# Ind_current_sensor_U.net
KiCad netlist of a schematic drawn in Altium Designer
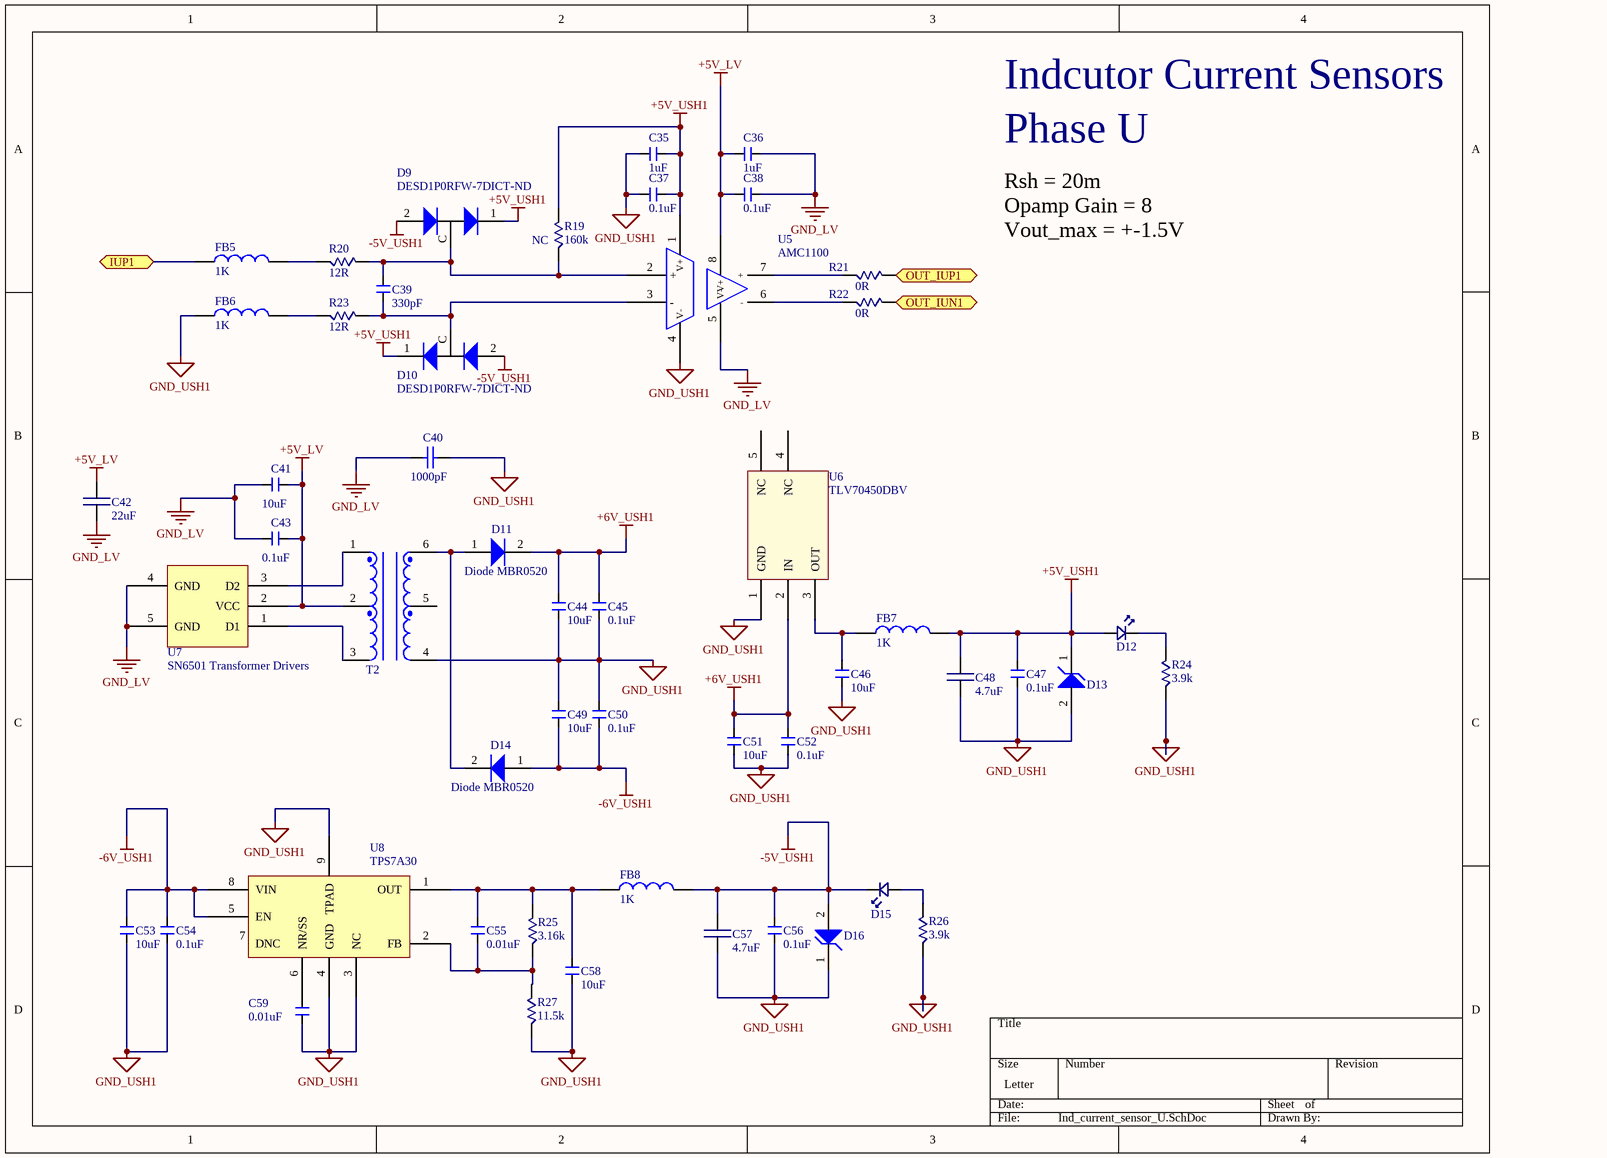
[diagram p0: Ind_current_sensor_U.SchDoc]

(export (version "E")
  (design (tool "Eeschema 10.0.6"))
  (components
    (comp (ref "C35")
      (value "1uF")
      (footprint "0603 (1608 Metric)")
      (description "CAP CER 1UF 50V X5R 0603")
      (fields (field (name "PART") "1276-1860-1-ND") (field (name "Comment") "Cap 0603_new"))
      (libsource (lib "Library_Microgrid") (part "Cap 0603_new"))
    )
    (comp (ref "C36")
      (value "1uF")
      (footprint "0603 (1608 Metric)")
      (description "CAP CER 1UF 50V X5R 0603")
      (fields (field (name "PART") "1276-1860-1-ND") (field (name "Comment") "Cap 0603_new"))
      (libsource (lib "Library_Microgrid") (part "Cap 0603_new"))
    )
    (comp (ref "C37")
      (value "0.1uF")
      (footprint "0603 (1608 Metric)")
      (description "CAP CER 0.1UF 50V Y5V 0603")
      (fields (field (name "PART") "311-1343-6-ND") (field (name "Comment") "Cap 0603_new"))
      (libsource (lib "Library_Microgrid") (part "Cap 0603_new"))
    )
    (comp (ref "C38")
      (value "0.1uF")
      (footprint "0603 (1608 Metric)")
      (description "CAP CER 0.1UF 50V Y5V 0603")
      (fields (field (name "PART") "311-1343-6-ND") (field (name "Comment") "Cap 0603_new"))
      (libsource (lib "Library_Microgrid") (part "Cap 0603_new"))
    )
    (comp (ref "C39")
      (value "330pF")
      (footprint "0603 (1608 Metric)")
      (description "CAP CER 330PF 50V C0G 0603")
      (fields (field (name "PART") "445-7033-2-ND") (field (name "Comment") "Cap 0603_new"))
      (libsource (lib "Library_Microgrid") (part "Cap 0603_new"))
    )
    (comp (ref "C40")
      (value "1000pF")
      (footprint "RAD-0.3")
      (description "CAP CER 1000PF 1KV Y5P RADIAL")
      (fields
        (field (name "PART") "1251PH-ND")
        (field (name "Comment") "Cap TH")
        (field (name "PUBLISHER") "Altium Limited")
      )
      (libsource (lib "Miscellaneous Devices") (part "Cap"))
    )
    (comp (ref "C41")
      (value "10uF")
      (footprint "0603 (1608 Metric)")
      (description "CAP CER 10UF 35V X5R 0805")
      (fields (field (name "PART") "490-10515-1-ND") (field (name "Comment") "Cap 0603_new"))
      (libsource (lib "Library_Microgrid") (part "Cap 0603_new"))
    )
    (comp (ref "C42")
      (value "22uF")
      (footprint "0805 (2012 metric)")
      (description "CAP CER 22UF 35V X5R 0805")
      (fields (field (name "PART") "445-14428-1-ND") (field (name "Comment") "Cap 0805"))
      (libsource (lib "Library_Microgrid") (part "Cap 0805"))
    )
    (comp (ref "C43")
      (value "0.1uF")
      (footprint "0603 (1608 Metric)")
      (description "CAP CER 0.1UF 50V Y5V 0603")
      (fields (field (name "PART") "311-1343-6-ND") (field (name "Comment") "Cap 0603_new"))
      (libsource (lib "Library_Microgrid") (part "Cap 0603_new"))
    )
    (comp (ref "C44")
      (value "10uF")
      (footprint "0603 (1608 Metric)")
      (description "CAP CER 10UF 35V X5R 0805")
      (fields (field (name "PART") "490-10515-1-ND") (field (name "Comment") "Cap 0603_new"))
      (libsource (lib "Library_Microgrid") (part "Cap 0603_new"))
    )
    (comp (ref "C45")
      (value "0.1uF")
      (footprint "0603 (1608 Metric)")
      (description "CAP CER 0.1UF 50V Y5V 0603")
      (fields (field (name "PART") "311-1343-6-ND") (field (name "Comment") "Cap 0603_new"))
      (libsource (lib "Library_Microgrid") (part "Cap 0603_new"))
    )
    (comp (ref "C46")
      (value "10uF")
      (footprint "0603 (1608 Metric)")
      (description "CAP CER 10UF 35V X5R 0805")
      (fields (field (name "PART") "490-10515-1-ND") (field (name "Comment") "Cap 0603_new"))
      (libsource (lib "Library_Microgrid") (part "Cap 0603_new"))
    )
    (comp (ref "C47")
      (value "0.1uF")
      (footprint "0603 (1608 Metric)")
      (description "CAP CER 0.1UF 50V Y5V 0603")
      (fields (field (name "PART") "311-1343-6-ND") (field (name "Comment") "Cap 0603_new"))
      (libsource (lib "Library_Microgrid") (part "Cap 0603_new"))
    )
    (comp (ref "C48")
      (value "4.7uF")
      (footprint "0805 (2012 metric)")
      (description "CAP CER 4.7UF 50V X5R 0805")
      (fields (field (name "PART") "445-5980-1-ND") (field (name "Comment") "Cap 0805"))
      (libsource (lib "Library_Microgrid") (part "Cap 0805"))
    )
    (comp (ref "C49")
      (value "10uF")
      (footprint "0603 (1608 Metric)")
      (description "CAP CER 10UF 35V X5R 0805")
      (fields (field (name "PART") "490-10515-1-ND") (field (name "Comment") "Cap 0603_new"))
      (libsource (lib "Library_Microgrid") (part "Cap 0603_new"))
    )
    (comp (ref "C50")
      (value "0.1uF")
      (footprint "0603 (1608 Metric)")
      (description "CAP CER 0.1UF 50V Y5V 0603")
      (fields (field (name "PART") "311-1343-6-ND") (field (name "Comment") "Cap 0603_new"))
      (libsource (lib "Library_Microgrid") (part "Cap 0603_new"))
    )
    (comp (ref "C51")
      (value "10uF")
      (footprint "0603 (1608 Metric)")
      (description "CAP CER 10UF 35V X5R 0805")
      (fields (field (name "PART") "490-10515-1-ND") (field (name "Comment") "Cap 0603_new"))
      (libsource (lib "Library_Microgrid") (part "Cap 0603_new"))
    )
    (comp (ref "C52")
      (value "0.1uF")
      (footprint "0603 (1608 Metric)")
      (description "CAP CER 0.1UF 50V Y5V 0603")
      (fields (field (name "PART") "311-1343-6-ND") (field (name "Comment") "Cap 0603_new"))
      (libsource (lib "Library_Microgrid") (part "Cap 0603_new"))
    )
    (comp (ref "C53")
      (value "10uF")
      (footprint "0603 (1608 Metric)")
      (description "CAP CER 10UF 35V X5R 0805")
      (fields (field (name "PART") "490-10515-1-ND") (field (name "Comment") "Cap 0603_new"))
      (libsource (lib "Library_Microgrid") (part "Cap 0603_new"))
    )
    (comp (ref "C54")
      (value "0.1uF")
      (footprint "0603 (1608 Metric)")
      (description "CAP CER 0.1UF 50V Y5V 0603")
      (fields (field (name "PART") "311-1343-6-ND") (field (name "Comment") "Cap 0603_new"))
      (libsource (lib "Library_Microgrid") (part "Cap 0603_new"))
    )
    (comp (ref "C55")
      (value "0.01uF")
      (footprint "0603 (1608 Metric)")
      (description "CAP CER 10000PF 100V X7R 0603")
      (fields (field (name "PART") "478-7418-1-ND") (field (name "Comment") "Cap 0603_new"))
      (libsource (lib "Library_Microgrid") (part "Cap 0603_new"))
    )
    (comp (ref "C56")
      (value "0.1uF")
      (footprint "0603 (1608 Metric)")
      (description "CAP CER 0.1UF 50V Y5V 0603")
      (fields (field (name "PART") "311-1343-6-ND") (field (name "Comment") "Cap 0603_new"))
      (libsource (lib "Library_Microgrid") (part "Cap 0603_new"))
    )
    (comp (ref "C57")
      (value "4.7uF")
      (footprint "0805 (2012 metric)")
      (description "CAP CER 4.7UF 50V X5R 0805")
      (fields (field (name "PART") "445-5980-1-ND") (field (name "Comment") "Cap 0805"))
      (libsource (lib "Library_Microgrid") (part "Cap 0805"))
    )
    (comp (ref "C58")
      (value "10uF")
      (footprint "0603 (1608 Metric)")
      (description "CAP CER 10UF 35V X5R 0805")
      (fields (field (name "PART") "490-10515-1-ND") (field (name "Comment") "Cap 0603_new"))
      (libsource (lib "Library_Microgrid") (part "Cap 0603_new"))
    )
    (comp (ref "C59")
      (value "0.01uF")
      (footprint "0603 (1608 Metric)")
      (description "CAP CER 10000PF 100V X7R 0603")
      (fields (field (name "PART") "478-7418-1-ND") (field (name "Comment") "Cap 0603_new"))
      (libsource (lib "Library_Microgrid") (part "Cap 0603_new"))
    )
    (comp (ref "D9")
      (value "TVS - Diodes")
      (footprint "SOT323_ESD")
      (description "TVS DIODE 70VWM 8VC SOT323")
      (fields (field (name "PART") "DESD1P0RFW-7DICT-ND"))
      (libsource (lib "Library_Microgrid") (part "Diode_ESD"))
    )
    (comp (ref "D10")
      (value "TVS - Diodes")
      (footprint "SOT323_ESD")
      (description "TVS DIODE 70VWM 8VC SOT323")
      (fields (field (name "PART") "DESD1P0RFW-7DICT-ND"))
      (libsource (lib "Library_Microgrid") (part "Diode_ESD"))
    )
    (comp (ref "D11")
      (value "Diode MBR0520")
      (footprint "SOD-123")
      (description "DIODE SCHOTTKY 20V 500MA SOD123")
      (fields (field (name "PART") "MBR0520LT1GOSCT-ND"))
      (libsource (lib "Library_Microgrid") (part "Diode MBR0520"))
    )
    (comp (ref "D12")
      (value "LED")
      (footprint "0805 (2012 Metric) Diode")
      (description "LED 0805")
      (libsource (lib "Library_Microgrid") (part "LED"))
    )
    (comp (ref "D13")
      (value "*")
      (footprint "POWERDI")
      (description "DIODE ZENER POWERDI123")
      (fields (field (name "PART") "MMSZ5228B-FDICT-ND"))
      (libsource (lib "Library_Microgrid") (part "Diode Zener POWERDI123"))
    )
    (comp (ref "D14")
      (value "Diode MBR0520")
      (footprint "SOD-123")
      (description "DIODE SCHOTTKY 20V 500MA SOD123")
      (fields (field (name "PART") "MBR0520LT1GOSCT-ND"))
      (libsource (lib "Library_Microgrid") (part "Diode MBR0520"))
    )
    (comp (ref "D15")
      (value "LED")
      (footprint "0805 (2012 Metric) Diode")
      (description "LED 0805")
      (libsource (lib "Library_Microgrid") (part "LED"))
    )
    (comp (ref "D16")
      (value "*")
      (footprint "POWERDI")
      (description "DIODE ZENER POWERDI123")
      (fields (field (name "PART") "MMSZ5228B-FDICT-ND"))
      (libsource (lib "Library_Microgrid") (part "Diode Zener POWERDI123"))
    )
    (comp (ref "FB5")
      (value "1K")
      (footprint "0603 (1608 Metric)")
      (description "FERRITE BEAD 1 KOHM 0603 1LN")
      (fields (field (name "PART") "445-8672-1-ND") (field (name "Comment") "Ferrite bead"))
      (libsource (lib "Library_Microgrid") (part "Ferrite bead"))
    )
    (comp (ref "FB6")
      (value "1K")
      (footprint "0603 (1608 Metric)")
      (description "FERRITE BEAD 1 KOHM 0603 1LN")
      (fields (field (name "PART") "445-8672-1-ND") (field (name "Comment") "Ferrite bead"))
      (libsource (lib "Library_Microgrid") (part "Ferrite bead"))
    )
    (comp (ref "FB7")
      (value "1K")
      (footprint "0603 (1608 Metric)")
      (description "FERRITE BEAD 1 KOHM 0603 1LN")
      (fields (field (name "PART") "445-8672-1-ND") (field (name "Comment") "Ferrite bead"))
      (libsource (lib "Library_Microgrid") (part "Ferrite bead"))
    )
    (comp (ref "FB8")
      (value "1K")
      (footprint "0603 (1608 Metric)")
      (description "FERRITE BEAD 1 KOHM 0603 1LN")
      (fields (field (name "PART") "445-8672-1-ND") (field (name "Comment") "Ferrite bead"))
      (libsource (lib "Library_Microgrid") (part "Ferrite bead"))
    )
    (comp (ref "R19")
      (value "NC")
      (footprint "0603 (1608 Metric)")
      (description "Resistor 0603")
      (fields (field (name "ALTIUM_VALUE") "160k"))
      (libsource (lib "Library_Microgrid") (part "Resistor 0603"))
    )
    (comp (ref "R20")
      (value "12R")
      (footprint "1206")
      (description "12 Ohm ±0.5% 0.25W, 1/4W Chip Resistor 1206")
      (fields (field (name "PART") "311-2961-1-ND") (field (name "Comment") "Resistor 1206"))
      (libsource (lib "Library_Microgrid") (part "Resistor 1206"))
    )
    (comp (ref "R21")
      (value "0R")
      (footprint "0603 (1608 Metric)")
      (description "RES SMD 10 OHM 0.05% 1/10W 0603")
      (fields (field (name "PART") "RNCF0603AKT10R0CT-ND") (field (name "Comment") "Resistor 0603"))
      (libsource (lib "Library_Microgrid") (part "Resistor 0603"))
    )
    (comp (ref "R22")
      (value "0R")
      (footprint "0603 (1608 Metric)")
      (description "RES SMD 10 OHM 0.05% 1/10W 0603")
      (fields (field (name "PART") "RNCF0603AKT10R0CT-ND") (field (name "Comment") "Resistor 0603"))
      (libsource (lib "Library_Microgrid") (part "Resistor 0603"))
    )
    (comp (ref "R23")
      (value "12R")
      (footprint "1206")
      (description "12 Ohm ±0.5% 0.25W, 1/4W Chip Resistor 1206")
      (fields (field (name "PART") "311-2961-1-ND") (field (name "Comment") "Resistor 1206"))
      (libsource (lib "Library_Microgrid") (part "Resistor 1206"))
    )
    (comp (ref "R24")
      (value "3.9k")
      (footprint "0603 (1608 Metric)")
      (description "RES SMD 3.9K OHM 5% 1/10W 0603")
      (fields (field (name "PART") "541-3.9KGCT-ND") (field (name "Comment") "Resistor 0603"))
      (libsource (lib "Library_Microgrid") (part "Resistor 0603"))
    )
    (comp (ref "R25")
      (value "3.16k")
      (footprint "0603 (1608 Metric)")
      (description "RES SMD 3.16K OHM 1% 1/10W 0603")
      (fields (field (name "PART") "311-3.16KHRCT-ND") (field (name "Comment") "Resistor 0603"))
      (libsource (lib "Library_Microgrid") (part "Resistor 0603"))
    )
    (comp (ref "R26")
      (value "3.9k")
      (footprint "0603 (1608 Metric)")
      (description "RES SMD 3.9K OHM 5% 1/10W 0603")
      (fields (field (name "PART") "541-3.9KGCT-ND") (field (name "Comment") "Resistor 0603"))
      (libsource (lib "Library_Microgrid") (part "Resistor 0603"))
    )
    (comp (ref "R27")
      (value "11.5k")
      (footprint "0603 (1608 Metric)")
      (description "RES SMD 11.5K OHM 1% 1/10W 0603")
      (fields (field (name "PART") "541-11.5KHCT-ND") (field (name "Comment") "Resistor 0603"))
      (libsource (lib "Library_Microgrid") (part "Resistor 0603"))
    )
    (comp (ref "T2")
      (value "750313769")
      (footprint "Xmr SN6501")
      (description "TRANSFORMER SMD TR1.7 SN6501")
      (fields (field (name "PART") "1297-1107-1-ND"))
      (libsource (lib "Library_Microgrid") (part "750313769"))
    )
    (comp (ref "U5")
      (value "AMC1100")
      (footprint "SOIC8")
      (description "IC OPAMP ISOLATION 100KHZ 8SOIC")
      (fields (field (name "PART") "296-38822-5-ND"))
      (libsource (lib "Library_Microgrid") (part "AMC1100"))
    )
    (comp (ref "U6")
      (value "TLV70450DBV")
      (footprint "SOT23-5")
      (description "IC REG LDO 5V 0.15A SOT23-5")
      (fields (field (name "PART") "296-39287-1-ND"))
      (libsource (lib "Library_Microgrid") (part "TLV70450DBV"))
    )
    (comp (ref "U7")
      (value "SN6501 Transformer Drivers")
      (footprint "SOT23-5")
      (description "IC REG CONV PWR SUPPLIES SOT23-5")
      (fields (field (name "PART") "296-37700-1-ND"))
      (libsource (lib "Library_Microgrid") (part "SN6501"))
    )
    (comp (ref "U8")
      (value "TPS7A30")
      (footprint "8-TSSOP")
      (description "IC REG LDO NEG ADJ 0.2A 8MSOP")
      (fields (field (name "PART") "296-27750-1-ND"))
      (libsource (lib "Library_Microgrid") (part "TPS7A30"))
    )
  )
  (nets
    (net (code "1") (name "+5V_LV") (class "Default")
      (node (ref "C36") (pin "1") (pinfunction "OUT_1") (pintype "passive"))
      (node (ref "C38") (pin "1") (pinfunction "OUT_1") (pintype "passive"))
      (node (ref "C41") (pin "2") (pinfunction "OUT_2") (pintype "passive"))
      (node (ref "C42") (pin "2") (pinfunction "OUT_2") (pintype "passive"))
      (node (ref "C43") (pin "2") (pinfunction "OUT_2") (pintype "passive"))
      (node (ref "T2") (pin "2") (pinfunction "1_2") (pintype "passive"))
      (node (ref "U5") (pin "8") (pinfunction "V+_8") (pintype "passive"))
      (node (ref "U7") (pin "2") (pinfunction "VCC_2") (pintype "passive"))
    )
    (net (code "2") (name "+5V_USH1") (class "Default")
      (node (ref "C35") (pin "2") (pinfunction "OUT_2") (pintype "passive"))
      (node (ref "C37") (pin "2") (pinfunction "OUT_2") (pintype "passive"))
      (node (ref "C47") (pin "2") (pinfunction "OUT_2") (pintype "passive"))
      (node (ref "C48") (pin "2") (pinfunction "OUT_2") (pintype "passive"))
      (node (ref "D10") (pin "1") (pinfunction "Anode_1") (pintype "passive"))
      (node (ref "D12") (pin "A") (pinfunction "A_A") (pintype "passive"))
      (node (ref "D13") (pin "1") (pinfunction "Anode_1") (pintype "passive"))
      (node (ref "D9") (pin "1") (pinfunction "Anode_1") (pintype "passive"))
      (node (ref "FB7") (pin "2") (pinfunction "OUT_2") (pintype "passive"))
      (node (ref "R19") (pin "2") (pinfunction "A_2") (pintype "passive"))
      (node (ref "U5") (pin "1") (pinfunction "V+_1") (pintype "passive"))
    )
    (net (code "3") (name "+6V_USH1") (class "Default")
      (node (ref "C44") (pin "2") (pinfunction "OUT_2") (pintype "passive"))
      (node (ref "C45") (pin "2") (pinfunction "OUT_2") (pintype "passive"))
      (node (ref "C51") (pin "2") (pinfunction "OUT_2") (pintype "passive"))
      (node (ref "C52") (pin "2") (pinfunction "OUT_2") (pintype "passive"))
      (node (ref "D11") (pin "2") (pinfunction "Anode_2") (pintype "passive"))
      (node (ref "U6") (pin "2") (pinfunction "IN_2") (pintype "passive"))
    )
    (net (code "4") (name "-5V_USH1") (class "Default")
      (node (ref "C56") (pin "2") (pinfunction "OUT_2") (pintype "passive"))
      (node (ref "C57") (pin "2") (pinfunction "OUT_2") (pintype "passive"))
      (node (ref "D10") (pin "2") (pinfunction "Anode_2") (pintype "passive"))
      (node (ref "D15") (pin "K") (pinfunction "K_K") (pintype "passive"))
      (node (ref "D16") (pin "2") (pinfunction "Anode_2") (pintype "passive"))
      (node (ref "D9") (pin "2") (pinfunction "Anode_2") (pintype "passive"))
      (node (ref "FB8") (pin "2") (pinfunction "OUT_2") (pintype "passive"))
    )
    (net (code "5") (name "-6V_USH1") (class "Default")
      (node (ref "C49") (pin "1") (pinfunction "OUT_1") (pintype "passive"))
      (node (ref "C50") (pin "1") (pinfunction "OUT_1") (pintype "passive"))
      (node (ref "C53") (pin "2") (pinfunction "OUT_2") (pintype "passive"))
      (node (ref "C54") (pin "2") (pinfunction "OUT_2") (pintype "passive"))
      (node (ref "D14") (pin "1") (pinfunction "Anode_1") (pintype "passive"))
      (node (ref "U8") (pin "5") (pinfunction "EN_5") (pintype "passive"))
      (node (ref "U8") (pin "8") (pinfunction "VIN_8") (pintype "power_in"))
    )
    (net (code "6") (name "/IUP1") (class "Default")
      (node (ref "FB5") (pin "1") (pinfunction "OUT_1") (pintype "passive"))
    )
    (net (code "7") (name "/OUT_IUN1") (class "Default")
      (node (ref "R22") (pin "2") (pinfunction "A_2") (pintype "passive"))
    )
    (net (code "8") (name "/OUT_IUP1") (class "Default")
      (node (ref "R21") (pin "2") (pinfunction "A_2") (pintype "passive"))
    )
    (net (code "9") (name "GND_LV") (class "Default")
      (node (ref "C36") (pin "2") (pinfunction "OUT_2") (pintype "passive"))
      (node (ref "C38") (pin "2") (pinfunction "OUT_2") (pintype "passive"))
      (node (ref "C40") (pin "1") (pinfunction "1_1") (pintype "passive"))
      (node (ref "C41") (pin "1") (pinfunction "OUT_1") (pintype "passive"))
      (node (ref "C42") (pin "1") (pinfunction "OUT_1") (pintype "passive"))
      (node (ref "C43") (pin "1") (pinfunction "OUT_1") (pintype "passive"))
      (node (ref "U5") (pin "5") (pinfunction "V-_5") (pintype "passive"))
      (node (ref "U7") (pin "4") (pinfunction "GND_4") (pintype "passive"))
      (node (ref "U7") (pin "5") (pinfunction "GND_5") (pintype "passive"))
    )
    (net (code "10") (name "GND_USH1") (class "Default")
      (node (ref "C35") (pin "1") (pinfunction "OUT_1") (pintype "passive"))
      (node (ref "C37") (pin "1") (pinfunction "OUT_1") (pintype "passive"))
      (node (ref "C40") (pin "2") (pinfunction "2_2") (pintype "passive"))
      (node (ref "C44") (pin "1") (pinfunction "OUT_1") (pintype "passive"))
      (node (ref "C45") (pin "1") (pinfunction "OUT_1") (pintype "passive"))
      (node (ref "C46") (pin "1") (pinfunction "OUT_1") (pintype "passive"))
      (node (ref "C47") (pin "1") (pinfunction "OUT_1") (pintype "passive"))
      (node (ref "C48") (pin "1") (pinfunction "OUT_1") (pintype "passive"))
      (node (ref "C49") (pin "2") (pinfunction "OUT_2") (pintype "passive"))
      (node (ref "C50") (pin "2") (pinfunction "OUT_2") (pintype "passive"))
      (node (ref "C51") (pin "1") (pinfunction "OUT_1") (pintype "passive"))
      (node (ref "C52") (pin "1") (pinfunction "OUT_1") (pintype "passive"))
      (node (ref "C53") (pin "1") (pinfunction "OUT_1") (pintype "passive"))
      (node (ref "C54") (pin "1") (pinfunction "OUT_1") (pintype "passive"))
      (node (ref "C56") (pin "1") (pinfunction "OUT_1") (pintype "passive"))
      (node (ref "C57") (pin "1") (pinfunction "OUT_1") (pintype "passive"))
      (node (ref "C58") (pin "1") (pinfunction "OUT_1") (pintype "passive"))
      (node (ref "C59") (pin "1") (pinfunction "OUT_1") (pintype "passive"))
      (node (ref "D13") (pin "2") (pinfunction "Anode_2") (pintype "passive"))
      (node (ref "D16") (pin "1") (pinfunction "Anode_1") (pintype "passive"))
      (node (ref "FB6") (pin "1") (pinfunction "OUT_1") (pintype "passive"))
      (node (ref "R24") (pin "1") (pinfunction "A_1") (pintype "passive"))
      (node (ref "R26") (pin "1") (pinfunction "A_1") (pintype "passive"))
      (node (ref "R27") (pin "1") (pinfunction "A_1") (pintype "passive"))
      (node (ref "T2") (pin "4") (pinfunction "1_4") (pintype "passive"))
      (node (ref "U5") (pin "4") (pinfunction "V-_4") (pintype "passive"))
      (node (ref "U6") (pin "1") (pinfunction "GND_1") (pintype "passive"))
      (node (ref "U8") (pin "3") (pinfunction "NC_3") (pintype "passive"))
      (node (ref "U8") (pin "4") (pinfunction "GND_4") (pintype "power_in"))
      (node (ref "U8") (pin "9") (pinfunction "TPAD_9") (pintype "power_in"))
    )
    (net (code "11") (name "Net-(D9-Cathode)") (class "Default")
      (node (ref "C39") (pin "1") (pinfunction "OUT_1") (pintype "passive"))
      (node (ref "D9") (pin "C") (pinfunction "Cathode_C") (pintype "passive"))
      (node (ref "R19") (pin "1") (pinfunction "A_1") (pintype "passive"))
      (node (ref "R20") (pin "2") (pinfunction "A_2") (pintype "passive"))
      (node (ref "U5") (pin "2") (pinfunction "+_2") (pintype "passive"))
    )
    (net (code "12") (name "Net-(D10-Cathode)") (class "Default")
      (node (ref "C39") (pin "2") (pinfunction "OUT_2") (pintype "passive"))
      (node (ref "D10") (pin "C") (pinfunction "Cathode_C") (pintype "passive"))
      (node (ref "R23") (pin "2") (pinfunction "A_2") (pintype "passive"))
      (node (ref "U5") (pin "3") (pinfunction "-_3") (pintype "passive"))
    )
    (net (code "13") (name "Net-(D11-Anode-Pad1)") (class "Default")
      (node (ref "D11") (pin "1") (pinfunction "Anode_1") (pintype "passive"))
      (node (ref "D14") (pin "2") (pinfunction "Anode_2") (pintype "passive"))
      (node (ref "T2") (pin "6") (pinfunction "1_6") (pintype "passive"))
    )
    (net (code "14") (name "Net-(D12-PadK)") (class "Default")
      (node (ref "D12") (pin "K") (pinfunction "K_K") (pintype "passive"))
      (node (ref "R24") (pin "2") (pinfunction "A_2") (pintype "passive"))
    )
    (net (code "15") (name "Net-(D15-PadA)") (class "Default")
      (node (ref "D15") (pin "A") (pinfunction "A_A") (pintype "passive"))
      (node (ref "R26") (pin "2") (pinfunction "A_2") (pintype "passive"))
    )
    (net (code "16") (name "Net-(FB5-OUT-Pad2)") (class "Default")
      (node (ref "FB5") (pin "2") (pinfunction "OUT_2") (pintype "passive"))
      (node (ref "R20") (pin "1") (pinfunction "A_1") (pintype "passive"))
    )
    (net (code "17") (name "Net-(FB6-OUT-Pad2)") (class "Default")
      (node (ref "FB6") (pin "2") (pinfunction "OUT_2") (pintype "passive"))
      (node (ref "R23") (pin "1") (pinfunction "A_1") (pintype "passive"))
    )
    (net (code "18") (name "Net-(R21-A-Pad1)") (class "Default")
      (node (ref "R21") (pin "1") (pinfunction "A_1") (pintype "passive"))
      (node (ref "U5") (pin "7") (pinfunction "+_7") (pintype "passive"))
    )
    (net (code "19") (name "Net-(R22-A-Pad1)") (class "Default")
      (node (ref "R22") (pin "1") (pinfunction "A_1") (pintype "passive"))
      (node (ref "U5") (pin "6") (pinfunction "-_6") (pintype "passive"))
    )
    (net (code "20") (name "Net-(U6-OUT)") (class "Default")
      (node (ref "C46") (pin "2") (pinfunction "OUT_2") (pintype "passive"))
      (node (ref "FB7") (pin "1") (pinfunction "OUT_1") (pintype "passive"))
      (node (ref "U6") (pin "3") (pinfunction "OUT_3") (pintype "passive"))
    )
    (net (code "21") (name "Net-(U7-D1)") (class "Default")
      (node (ref "T2") (pin "3") (pinfunction "1_3") (pintype "passive"))
      (node (ref "U7") (pin "1") (pinfunction "D1_1") (pintype "passive"))
    )
    (net (code "22") (name "Net-(U7-D2)") (class "Default")
      (node (ref "T2") (pin "1") (pinfunction "1_1") (pintype "passive"))
      (node (ref "U7") (pin "3") (pinfunction "D2_3") (pintype "passive"))
    )
    (net (code "23") (name "Net-(U8-FB)") (class "Default")
      (node (ref "C55") (pin "2") (pinfunction "OUT_2") (pintype "passive"))
      (node (ref "R25") (pin "1") (pinfunction "A_1") (pintype "passive"))
      (node (ref "R27") (pin "2") (pinfunction "A_2") (pintype "passive"))
      (node (ref "U8") (pin "2") (pinfunction "FB_2") (pintype "passive"))
    )
    (net (code "24") (name "Net-(U8-NR{slash}SS)") (class "Default")
      (node (ref "C59") (pin "2") (pinfunction "OUT_2") (pintype "passive"))
      (node (ref "U8") (pin "6") (pinfunction "NR/SS_6") (pintype "power_in"))
    )
    (net (code "25") (name "Net-(U8-OUT)") (class "Default")
      (node (ref "C55") (pin "1") (pinfunction "OUT_1") (pintype "passive"))
      (node (ref "C58") (pin "2") (pinfunction "OUT_2") (pintype "passive"))
      (node (ref "FB8") (pin "1") (pinfunction "OUT_1") (pintype "passive"))
      (node (ref "R25") (pin "2") (pinfunction "A_2") (pintype "passive"))
      (node (ref "U8") (pin "1") (pinfunction "OUT_1") (pintype "passive"))
    )
    (net (code "26") (name "unconnected-(T2-1-Pad5)") (class "Default")
      (node (ref "T2") (pin "5") (pinfunction "1_5") (pintype "passive"))
    )
    (net (code "27") (name "unconnected-(U6-NC-Pad4)") (class "Default")
      (node (ref "U6") (pin "4") (pinfunction "NC_4") (pintype "passive"))
    )
    (net (code "28") (name "unconnected-(U6-NC-Pad5)") (class "Default")
      (node (ref "U6") (pin "5") (pinfunction "NC_5") (pintype "passive"))
    )
    (net (code "29") (name "unconnected-(U8-DNC-Pad7)") (class "Default")
      (node (ref "U8") (pin "7") (pinfunction "DNC_7") (pintype "passive"))
    )
  )
)
